# lightamp.net
KiCad netlist of a schematic drawn in EAGLE
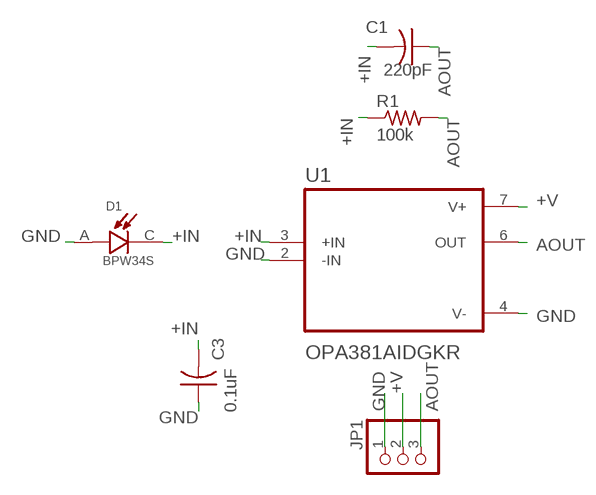
[diagram p0: schematic, sheet 1]

(export (version "E")
  (design (tool "Eeschema 10.0.6"))
  (components
    (comp (ref "C1")
      (value "220pF")
      (footprint "eagle-import:C025-025X050")
      (libsource (lib "eagle-import") (part "C-US025-025X050"))
    )
    (comp (ref "C3")
      (value "0.1uF")
      (footprint "eagle-import:C025-025X050")
      (libsource (lib "eagle-import") (part "C-US025-025X050"))
    )
    (comp (ref "D1")
      (value "BPW34S")
      (footprint "eagle-import:DIO_BPW34S")
      (fields (field (name "MF") "Vishay Semiconductor Opto Division"))
      (libsource (lib "eagle-import") (part "BPW34S"))
    )
    (comp (ref "JP1")
      (value "PINHD-1X3")
      (footprint "eagle-import:1X03")
      (libsource (lib "eagle-import") (part "PINHD-1X3"))
    )
    (comp (ref "R1")
      (value "100k")
      (footprint "eagle-import:0204_5")
      (libsource (lib "eagle-import") (part "R-US_0204/5"))
    )
    (comp (ref "U1")
      (value "OPA381AIDGKR")
      (footprint "eagle-import:SOP65P490X110-8N")
      (fields (field (name "MF") "Texas Instruments"))
      (libsource (lib "eagle-import") (part "OPA381AIDGKR"))
    )
  )
  (nets
    (net (code "1") (name "/+IN") (class "Default")
      (node (ref "C1") (pin "2") (pinfunction "2_2") (pintype "passive"))
      (node (ref "C3") (pin "2") (pinfunction "2_2") (pintype "passive"))
      (node (ref "D1") (pin "C") (pinfunction "C_C") (pintype "passive"))
      (node (ref "R1") (pin "1") (pinfunction "1_1") (pintype "passive"))
      (node (ref "U1") (pin "3") (pinfunction "+IN_3") (pintype "input"))
    )
    (net (code "2") (name "/+V") (class "Default")
      (node (ref "JP1") (pin "2") (pinfunction "2_2") (pintype "passive"))
      (node (ref "U1") (pin "7") (pinfunction "V+_7") (pintype "power_in"))
    )
    (net (code "3") (name "/AOUT") (class "Default")
      (node (ref "C1") (pin "1") (pinfunction "1_1") (pintype "passive"))
      (node (ref "JP1") (pin "3") (pinfunction "3_3") (pintype "passive"))
      (node (ref "R1") (pin "2") (pinfunction "2_2") (pintype "passive"))
      (node (ref "U1") (pin "6") (pinfunction "OUT_6") (pintype "output"))
    )
    (net (code "4") (name "/GND") (class "Default")
      (node (ref "C3") (pin "1") (pinfunction "1_1") (pintype "passive"))
      (node (ref "D1") (pin "A") (pinfunction "A_A") (pintype "passive"))
      (node (ref "JP1") (pin "1") (pinfunction "1_1") (pintype "passive"))
      (node (ref "U1") (pin "2") (pinfunction "-IN_2") (pintype "input"))
      (node (ref "U1") (pin "4") (pinfunction "V-_4") (pintype "power_in"))
    )
  )
)
